# tesis_page1_supply.net
KiCad netlist of a schematic drawn in Altium Designer
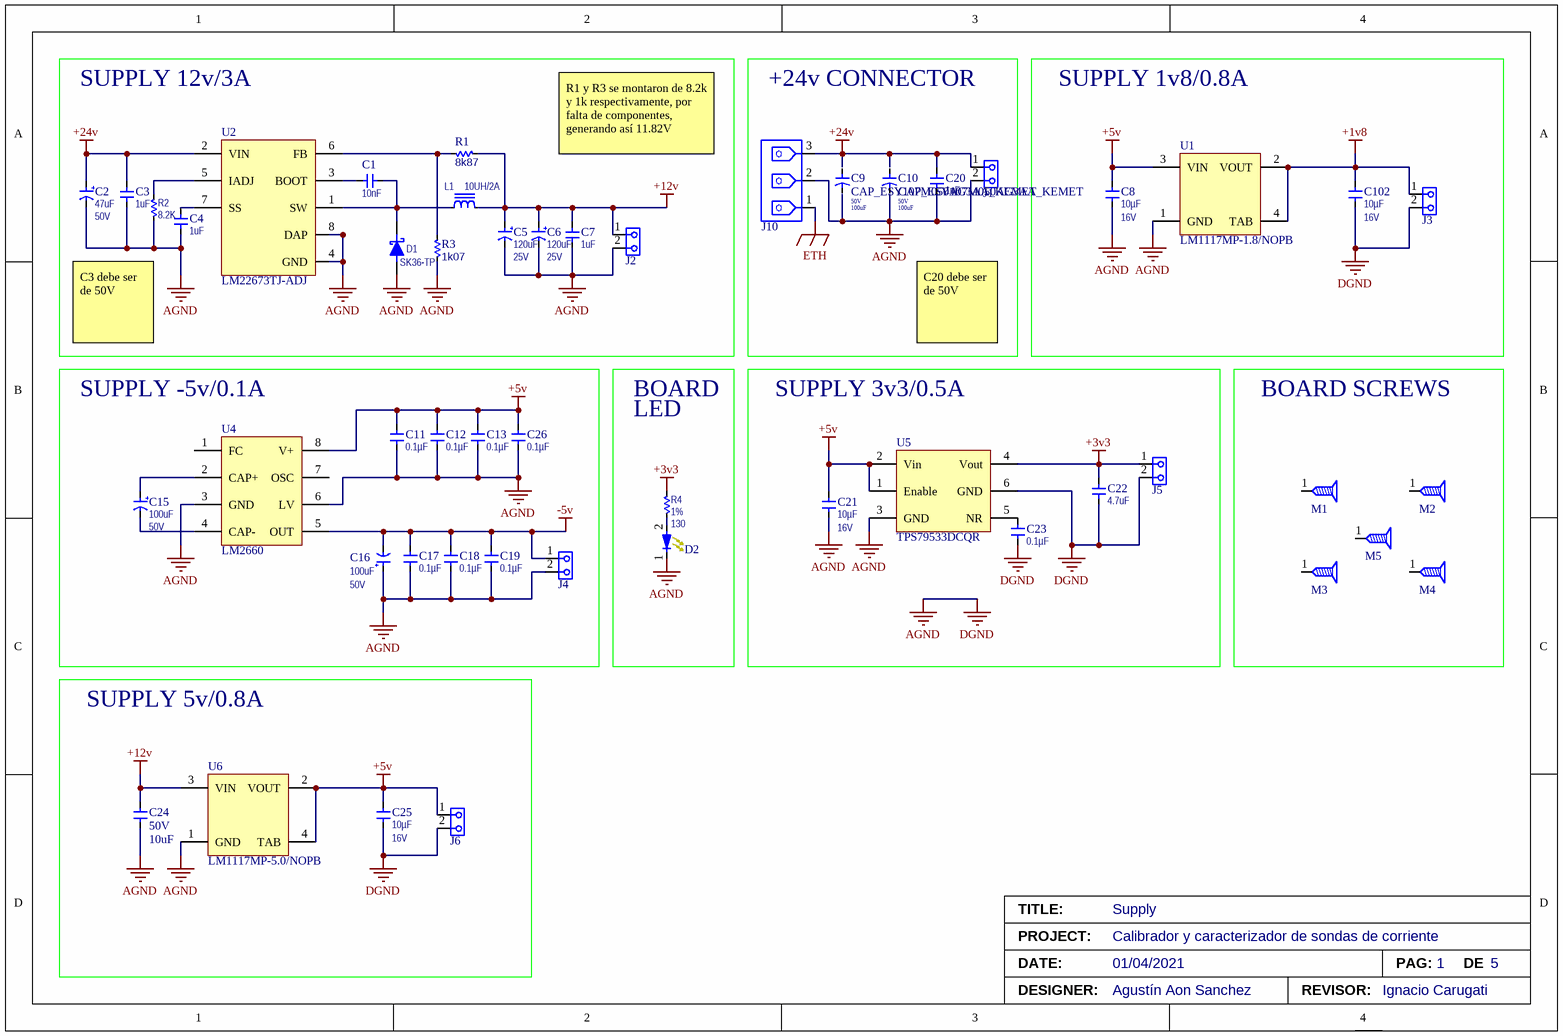
[diagram p0: tesis_page1_supply.SchDoc]

(export (version "E")
  (design (tool "Eeschema 10.0.6"))
  (components
    (comp (ref "C1")
      (value "10nF")
      (footprint "CAPC3216X135N_B")
      (fields
        (field (name "MANUFACTURER") "TDK")
        (field (name "TOLERANCE") "10%")
        (field (name "DIGIKEY PART NUMBER") "445-2291-1-ND")
      )
      (libsource (lib "pqm_v2_lib_cap") (part "CAP_C3216X7R2J103K115AA_TDK"))
    )
    (comp (ref "C2")
      (value "47uF")
      (footprint "CAPAE630770X770N")
      (description "47µF 50V Aluminum Capacitors Radial, Can - SMD 2000 Hrs @ 85°C")
      (fields
        (field (name "MANUFACTURER") "Panasonic")
        (field (name "TOLERANCE") "20%")
        (field (name "VOLTAGE RATING") "50V")
      )
      (libsource (lib "pqm_v2_lib_cap") (part "CAP_EEE-1HA470XP_PANASONIC"))
    )
    (comp (ref "C3")
      (value "1uF")
      (footprint "CAPC3216X135N_B")
      (fields
        (field (name "MANUFACTURER") "TDK")
        (field (name "TOLERANCE") "20%")
        (field (name "DIGIKEY PART NUMBER") "445-4024-1-ND")
      )
      (libsource (lib "pqm_v2_lib_cap") (part "CAP_C3216X7R1E105M085AA_TDK"))
    )
    (comp (ref "C4")
      (value "1uF")
      (footprint "CAPC3216X135N_B")
      (fields
        (field (name "MANUFACTURER") "TDK")
        (field (name "TOLERANCE") "20%")
        (field (name "DIGIKEY PART NUMBER") "445-4024-1-ND")
      )
      (libsource (lib "pqm_v2_lib_cap") (part "CAP_C3216X7R1E105M085AA_TDK"))
    )
    (comp (ref "C5")
      (value "120uF")
      (footprint "CAPPRD250W50D630H1250")
      (description "CAP ALUM 120UF 20% 25V RADIAL")
      (fields
        (field (name "DIGIKEY PART NUMBER") "565-1791-ND")
        (field (name "TOLERANCE") "20%")
        (field (name "VOLTAGE RATING") "25V")
      )
      (libsource (lib "pqm_v2_lib_cap") (part "CAP_ELXY250ELL121MF15D_UC"))
    )
    (comp (ref "C6")
      (value "120uF")
      (footprint "CAPPRD250W50D630H1250")
      (description "CAP ALUM 120UF 20% 25V RADIAL")
      (fields
        (field (name "DIGIKEY PART NUMBER") "565-1791-ND")
        (field (name "TOLERANCE") "20%")
        (field (name "VOLTAGE RATING") "25V")
      )
      (libsource (lib "pqm_v2_lib_cap") (part "CAP_ELXY250ELL121MF15D_UC"))
    )
    (comp (ref "C7")
      (value "1uF")
      (footprint "CAPC3216X135N_B")
      (fields
        (field (name "MANUFACTURER") "TDK")
        (field (name "TOLERANCE") "20%")
        (field (name "DIGIKEY PART NUMBER") "445-4024-1-ND")
      )
      (libsource (lib "pqm_v2_lib_cap") (part "CAP_C3216X7R1E105M085AA_TDK"))
    )
    (comp (ref "C8")
      (value "10µF")
      (footprint "CAPC2013X110N")
      (description "CAP CER 10UF 16V X5R 0805")
      (fields
        (field (name "MANUFACTURER") "Samsung")
        (field (name "TOLERANCE") "10%")
        (field (name "VOLTAGE RATING") "16V")
      )
      (libsource (lib "lib_ic_CAP") (part "CAP_CL21A106KOCL3RC"))
    )
    (comp (ref "C9")
      (value "CAP_ESY107M050AG3AA_KEMET")
      (footprint "cap elec 8x11.5")
      (fields
        (field (name "TOLERANCE") "20%")
        (field (name "VOLTAGE") "50V")
        (field (name "CAPACITANCE") "100uF")
      )
      (libsource (lib "Cap") (part "CAP_ESY107M050AG3AA_KEMET"))
    )
    (comp (ref "C10")
      (value "CAP_ESY107M050AG3AA_KEMET")
      (footprint "cap elec 8x11.5")
      (fields
        (field (name "TOLERANCE") "20%")
        (field (name "VOLTAGE") "50V")
        (field (name "CAPACITANCE") "100uF")
      )
      (libsource (lib "Cap") (part "CAP_ESY107M050AG3AA_KEMET"))
    )
    (comp (ref "C11")
      (value "0.1µF")
      (footprint "CAPC2013X110N")
      (description "CAP CER 0.1UF 25V 10% X7R 0805")
      (fields (field (name "MANUFACTURER") "Yageo") (field (name "DIGIKEY PART NUMBER") "311-1141-1-ND"))
      (libsource (lib "lib_ic_CAP") (part "CAP_CC0805KRX7R8BB104_YAGEO"))
    )
    (comp (ref "C12")
      (value "0.1µF")
      (footprint "CAPC2013X110N")
      (description "CAP CER 0.1UF 25V 10% X7R 0805")
      (fields (field (name "MANUFACTURER") "Yageo") (field (name "DIGIKEY PART NUMBER") "311-1141-1-ND"))
      (libsource (lib "lib_ic_CAP") (part "CAP_CC0805KRX7R8BB104_YAGEO"))
    )
    (comp (ref "C13")
      (value "0.1µF")
      (footprint "CAPC2013X110N")
      (description "CAP CER 0.1UF 25V 10% X7R 0805")
      (fields (field (name "MANUFACTURER") "Yageo") (field (name "DIGIKEY PART NUMBER") "311-1141-1-ND"))
      (libsource (lib "lib_ic_CAP") (part "CAP_CC0805KRX7R8BB104_YAGEO"))
    )
    (comp (ref "C15")
      (value "100uF")
      (footprint "CAPPRD350W60D800H1200")
      (description "CAP ALUM 100UF 20% 50V RADIAL")
      (fields
        (field (name "DIGIKEY PART NUMBER") "399-6119-ND")
        (field (name "TOLERANCE") "20%")
        (field (name "VOLTAGE RATING") "50V")
      )
      (libsource (lib "lib_ic_CAP") (part "CAP_   ESY107M050AG3AA_KEMET"))
    )
    (comp (ref "C16")
      (value "100uF")
      (footprint "CAPPRD350W60D800H1200")
      (description "CAP ALUM 100UF 20% 50V RADIAL")
      (fields
        (field (name "DIGIKEY PART NUMBER") "399-6119-ND")
        (field (name "TOLERANCE") "20%")
        (field (name "VOLTAGE RATING") "50V")
      )
      (libsource (lib "lib_ic_CAP") (part "CAP_   ESY107M050AG3AA_KEMET"))
    )
    (comp (ref "C17")
      (value "0.1µF")
      (footprint "CAPC2013X110N")
      (description "CAP CER 0.1UF 25V 10% X7R 0805")
      (fields (field (name "MANUFACTURER") "Yageo") (field (name "DIGIKEY PART NUMBER") "311-1141-1-ND"))
      (libsource (lib "lib_ic_CAP") (part "CAP_CC0805KRX7R8BB104_YAGEO"))
    )
    (comp (ref "C18")
      (value "0.1µF")
      (footprint "CAPC2013X110N")
      (description "CAP CER 0.1UF 25V 10% X7R 0805")
      (fields (field (name "MANUFACTURER") "Yageo") (field (name "DIGIKEY PART NUMBER") "311-1141-1-ND"))
      (libsource (lib "lib_ic_CAP") (part "CAP_CC0805KRX7R8BB104_YAGEO"))
    )
    (comp (ref "C19")
      (value "0.1µF")
      (footprint "CAPC2013X110N")
      (description "CAP CER 0.1UF 25V 10% X7R 0805")
      (fields (field (name "MANUFACTURER") "Yageo") (field (name "DIGIKEY PART NUMBER") "311-1141-1-ND"))
      (libsource (lib "lib_ic_CAP") (part "CAP_CC0805KRX7R8BB104_YAGEO"))
    )
    (comp (ref "C20")
      (value "1uF")
      (footprint "CAPC3216X135N_B")
      (fields
        (field (name "MANUFACTURER") "TDK")
        (field (name "TOLERANCE") "20%")
        (field (name "DIGIKEY PART NUMBER") "445-4024-1-ND")
      )
      (libsource (lib "lib_ic_CAP") (part "CAP_C3216X7R1E105M085AA_TDK"))
    )
    (comp (ref "C21")
      (value "10µF")
      (footprint "CAPC2013X110N")
      (description "CAP CER 10UF 16V X5R 0805")
      (fields
        (field (name "MANUFACTURER") "Samsung")
        (field (name "TOLERANCE") "10%")
        (field (name "VOLTAGE RATING") "16V")
      )
      (libsource (lib "lib_ic_CAP") (part "CAP_CL21A106KOCL3RC"))
    )
    (comp (ref "C22")
      (value "4.7uF")
      (footprint "CAPC2013X110N")
      (description "CAP CER 4.7UF 25V X5R 0805")
      (fields (field (name "MANUFACTURER") "YAGEO") (field (name "TOLERANCE") "10%"))
      (libsource (lib "lib_ic_CAP") (part "CAP_CC0805KKX5R8BB475_YAGEO_1"))
    )
    (comp (ref "C23")
      (value "0.1µF")
      (footprint "CAPC2013X110N")
      (description "CAP CER 0.1UF 25V 10% X7R 0805")
      (fields (field (name "MANUFACTURER") "Yageo") (field (name "DIGIKEY PART NUMBER") "311-1141-1-ND"))
      (libsource (lib "lib_ic_CAP") (part "CAP_CC0805KRX7R8BB104_YAGEO"))
    )
    (comp (ref "C24")
      (value "10uF")
      (footprint "CAPC3216X135N_B")
      (description "Cap Ceramic 10uF 50V X5R 20% Pad SMD 1206 85C Automotive T/R")
      (fields
        (field (name "MANUFACTURER") "Murata")
        (field (name "TOLERANCE") "20%")
        (field (name "VOLTAGE RATING") "50V")
      )
      (libsource (lib "lib_ic_CAP") (part "CAP_GRT31CR61H106ME01L"))
    )
    (comp (ref "C25")
      (value "10µF")
      (footprint "CAPC2013X110N")
      (description "CAP CER 10UF 16V X5R 0805")
      (fields
        (field (name "MANUFACTURER") "Samsung")
        (field (name "TOLERANCE") "10%")
        (field (name "VOLTAGE RATING") "16V")
      )
      (libsource (lib "lib_ic_CAP") (part "CAP_CL21A106KOCL3RC"))
    )
    (comp (ref "C26")
      (value "0.1µF")
      (footprint "CAPC2013X110N")
      (description "CAP CER 0.1UF 25V 10% X7R 0805")
      (fields (field (name "MANUFACTURER") "Yageo") (field (name "DIGIKEY PART NUMBER") "311-1141-1-ND"))
      (libsource (lib "lib_ic_CAP") (part "CAP_CC0805KRX7R8BB104_YAGEO"))
    )
    (comp (ref "C102")
      (value "10µF")
      (footprint "CAPC2013X110N")
      (description "CAP CER 10UF 16V X5R 0805")
      (fields
        (field (name "MANUFACTURER") "Samsung")
        (field (name "TOLERANCE") "10%")
        (field (name "VOLTAGE RATING") "16V")
      )
      (libsource (lib "lib_ic_CAP") (part "CAP_CL21A106KOCL3RC"))
    )
    (comp (ref "D1")
      (value "SK36-TP")
      (footprint "DIOM7959X262N")
      (description "DIODE SCHOTTKY 60V 3A SMC")
      (fields
        (field (name "MANUFACTURER") "Micro Commercial Co")
        (field (name "DIGIKEY PART NUMBER") "SK36-TPMSCT-ND")
      )
      (libsource (lib "lib_ic_DIO") (part "DIO_SK36_MICROCOM"))
    )
    (comp (ref "D2")
      (value "DIO_150080YS75000_WURTH")
      (footprint "DIO0805")
      (description "LED YELLOW CLEAR 0805 SMD")
      (fields
        (field (name "MANUFACTURER") "Wurth Electronics Inc.")
        (field (name "MANUFACTURER PART NUMBER") "150080YS75000")
      )
      (libsource (lib "lib_ic_DIO") (part "DIO_150080YS75000_WURTH"))
    )
    (comp (ref "J1")
      (value "CON_Header_1x2")
      (footprint "RAD2")
      (libsource (lib "lib_ic_CON") (part "CON_Header_1x2"))
    )
    (comp (ref "J2")
      (value "CON_Header_1x2")
      (footprint "RAD2")
      (libsource (lib "lib_ic_CON") (part "CON_Header_1x2"))
    )
    (comp (ref "J3")
      (value "CON_Header_1x2")
      (footprint "RAD2")
      (libsource (lib "lib_ic_CON") (part "CON_Header_1x2"))
    )
    (comp (ref "J4")
      (value "CON_Header_1x2")
      (footprint "RAD2")
      (libsource (lib "lib_ic_CON") (part "CON_Header_1x2"))
    )
    (comp (ref "J5")
      (value "CON_Header_1x2")
      (footprint "RAD2")
      (libsource (lib "lib_ic_CON") (part "CON_Header_1x2"))
    )
    (comp (ref "J6")
      (value "CON_Header_1x2")
      (footprint "RAD2")
      (libsource (lib "lib_ic_CON") (part "CON_Header_1x2"))
    )
    (comp (ref "J10")
      (value "CON_691137710003")
      (footprint "CON_691137710003")
      (description "TERM BLK 3POS SIDE ENTRY 5MM PCB")
      (fields
        (field (name "MANUFACTURER") "Wurth Electronics")
        (field (name "MANUFACTURER PART NUMBER") "691137710003")
      )
      (libsource (lib "lib_ic_CON") (part "CON_691137710003"))
    )
    (comp (ref "L1")
      (value "10UH/2A")
      (footprint "MAG_INDUCTOR2A")
      (description "FIXED IND 10UH 2A 65 MOHM SMD")
      (fields
        (field (name "MANUFACTURER") "Bourns Inc")
        (field (name "DIGIKEY PART NUMBER") "SRR1005-100MCT-ND")
      )
      (libsource (lib "pqm_v2_lib_mag") (part "MAG_SRR1005-100M_BOURNS"))
    )
    (comp (ref "M1")
      (value "MSC_SCREW")
      (footprint "MH320")
      (description "SCREW")
      (libsource (lib "lib_ic_MSC") (part "MSC_SCREW"))
    )
    (comp (ref "M2")
      (value "MSC_SCREW")
      (footprint "MH320")
      (description "SCREW")
      (libsource (lib "lib_ic_MSC") (part "MSC_SCREW"))
    )
    (comp (ref "M3")
      (value "MSC_SCREW")
      (footprint "MH320")
      (description "SCREW")
      (libsource (lib "lib_ic_MSC") (part "MSC_SCREW"))
    )
    (comp (ref "M4")
      (value "MSC_SCREW")
      (footprint "MH320")
      (description "SCREW")
      (libsource (lib "lib_ic_MSC") (part "MSC_SCREW"))
    )
    (comp (ref "M5")
      (value "MSC_SCREW")
      (footprint "MH320")
      (description "SCREW")
      (libsource (lib "lib_ic_MSC") (part "MSC_SCREW"))
    )
    (comp (ref "R1")
      (value "8k87")
      (footprint "RESC2013X065BN")
      (description "Res Thick Film 0805 8.87K Ohm 1% 0.125W(1/8W) ±100ppm/C Epoxy Pad SMD T/R")
      (fields
        (field (name "MANUFACTURER") "Yageo")
        (field (name "MANUFACTURER PART NUMBER") "RC0805FR-078K87L")
      )
      (libsource (lib "lib_ic_RES") (part "RES_RC0805FR-078K87L"))
    )
    (comp (ref "R2")
      (value "8.2K")
      (footprint "RESC3216N")
      (description "RES SMD 8.2K OHM 5% 1/4W 1206")
      (fields (field (name "TOLERANCE") "5%") (field (name "MANUFACTURER") "Panasonic"))
      (libsource (lib "pqm_v2_lib_res") (part "RES_ERJ-8GEYJ822V_Panasonic"))
    )
    (comp (ref "R3")
      (value "1k07")
      (footprint "RESC2013X065BN")
      (description "Res Thick Film 0805 1.07K Ohm 1% 1/8W 100ppm/C Molded SMD Paper T/R")
      (fields
        (field (name "MANUFACTURER") "Yageo")
        (field (name "MANUFACTURER PART NUMBER") "RC0805FR-071K07L")
      )
      (libsource (lib "lib_ic_RES") (part "RES_RC0805FR-071K07L"))
    )
    (comp (ref "R4")
      (value "130")
      (footprint "RESC2013X065BN")
      (description "RES SMD 130 OHM 1% 1/8W 0805")
      (fields
        (field (name "MANUFACTURER") "Yageo")
        (field (name "DIGIKEY PART NUMBER") "311-130CRCT-ND")
        (field (name "TOLERANCE") "1%")
      )
      (libsource (lib "lib_ic_RES") (part "RES_RC0805FR-07130RL_YAGEO"))
    )
    (comp (ref "U1")
      (value "LM1117MP-1.8/NOPB")
      (footprint "SOT223-3L")
      (description "IC REG LDO 1.8V .8A SOT-223-4")
      (fields (field (name "MANUFACTURER") "TI National Semiconductor"))
      (libsource (lib "lib_ic_IC") (part "IC_LM1117MP-1.8/NOPB"))
    )
    (comp (ref "U2")
      (value "LM22673TJ-ADJ")
      (footprint "TJ7A_N")
      (fields
        (field (name "DIGIKEY PART NUMBER") "LM22673TJ-ADJ/NOPBCT-ND")
        (field (name "MANUFACTURER PART NUMBER") "LM22673TJ-ADJ/NOPB")
        (field (name "MOUSER PART NUMBER") "926-LM22673TJADJNOPB")
      )
      (libsource (lib "lib_ic_IC") (part "IC_LM22673TJ-ADJ"))
    )
    (comp (ref "U4")
      (value "LM2660")
      (footprint "SOIC127P600-8BN")
      (description "IC REG SWTCHD CAP INV 0.1A 8SOIC")
      (fields
        (field (name "DIGIKEY PART NUMBER") "LM2660MX/NOPBCT-ND")
        (field (name "MANUFACTURER PART NUMBER") "LM2660MX/NOPB")
      )
      (libsource (lib "lib_ic_IC") (part "IC_LM2660MX/NOPB_1"))
    )
    (comp (ref "U5")
      (value "TPS79533DCQR")
      (footprint "SOT223-6L")
      (description "IC REG LIN 3.3V 500MA SOT223-6")
      (fields
        (field (name "DIGIKEY PART NUMBER") "296-13810-1-ND")
        (field (name "MANUFACTURER PART NUMBER") "595-TPS79533DCQR")
      )
      (libsource (lib "lib_ic_IC") (part "IC_TPS79533DCQR_TI"))
    )
    (comp (ref "U6")
      (value "LM1117MP-5.0/NOPB")
      (footprint "SOT223-3L")
      (description "IC REG LDO 5V .8A SOT-223-4")
      (fields (field (name "MANUFACTURER") "TI National Semiconductor"))
      (libsource (lib "lib_ic_IC") (part "IC_LM1117MP-5.0/NOPB"))
    )
  )
  (nets
    (net (code "1") (name "+1v8") (class "Default")
      (node (ref "C102") (pin "1") (pinfunction "T1_1") (pintype "passive"))
      (node (ref "J3") (pin "1") (pinfunction "1_1") (pintype "passive"))
      (node (ref "U1") (pin "2") (pinfunction "VOUT_2") (pintype "passive"))
      (node (ref "U1") (pin "4") (pinfunction "TAB_4") (pintype "passive"))
    )
    (net (code "2") (name "+3v3") (class "Default")
      (node (ref "C22") (pin "1") (pinfunction "T1_1") (pintype "passive"))
      (node (ref "J5") (pin "1") (pinfunction "1_1") (pintype "passive"))
      (node (ref "R4") (pin "2") (pinfunction "T2_2") (pintype "passive"))
      (node (ref "U5") (pin "4") (pinfunction "Vout_4") (pintype "passive"))
    )
    (net (code "3") (name "+5v") (class "Default")
      (node (ref "C11") (pin "1") (pinfunction "T1_1") (pintype "passive"))
      (node (ref "C12") (pin "1") (pinfunction "T1_1") (pintype "passive"))
      (node (ref "C13") (pin "1") (pinfunction "T1_1") (pintype "passive"))
      (node (ref "C21") (pin "1") (pinfunction "T1_1") (pintype "passive"))
      (node (ref "C25") (pin "1") (pinfunction "T1_1") (pintype "passive"))
      (node (ref "C26") (pin "1") (pinfunction "T1_1") (pintype "passive"))
      (node (ref "C8") (pin "1") (pinfunction "T1_1") (pintype "passive"))
      (node (ref "J6") (pin "1") (pinfunction "1_1") (pintype "passive"))
      (node (ref "U1") (pin "3") (pinfunction "VIN_3") (pintype "passive"))
      (node (ref "U4") (pin "8") (pinfunction "V+_8") (pintype "passive"))
      (node (ref "U5") (pin "1") (pinfunction "Enable_1") (pintype "passive"))
      (node (ref "U5") (pin "2") (pinfunction "Vin_2") (pintype "passive"))
      (node (ref "U6") (pin "2") (pinfunction "VOUT_2") (pintype "passive"))
      (node (ref "U6") (pin "4") (pinfunction "TAB_4") (pintype "passive"))
    )
    (net (code "4") (name "+12v") (class "Default")
      (node (ref "C24") (pin "1") (pinfunction "T1_1") (pintype "passive"))
      (node (ref "C5") (pin "1") (pinfunction "1_1") (pintype "passive"))
      (node (ref "C6") (pin "1") (pinfunction "1_1") (pintype "passive"))
      (node (ref "C7") (pin "1") (pinfunction "T1_1") (pintype "passive"))
      (node (ref "J2") (pin "1") (pinfunction "1_1") (pintype "passive"))
      (node (ref "L1") (pin "2") (pinfunction "2_2") (pintype "passive"))
      (node (ref "R1") (pin "1") (pinfunction "T1_1") (pintype "passive"))
      (node (ref "U6") (pin "3") (pinfunction "VIN_3") (pintype "passive"))
    )
    (net (code "5") (name "+24v") (class "Default")
      (node (ref "C2") (pin "1") (pinfunction "1_1") (pintype "passive"))
      (node (ref "C20") (pin "1") (pinfunction "T1_1") (pintype "passive"))
      (node (ref "C3") (pin "1") (pinfunction "T1_1") (pintype "passive"))
      (node (ref "J1") (pin "1") (pinfunction "1_1") (pintype "passive"))
      (node (ref "J10") (pin "3") (pinfunction "3_3") (pintype "passive"))
      (node (ref "U2") (pin "2") (pinfunction "VIN_2") (pintype "power_in"))
    )
    (net (code "6") (name "-5v") (class "Default")
      (node (ref "C16") (pin "2") (pinfunction "2_2") (pintype "passive"))
      (node (ref "C17") (pin "1") (pinfunction "T1_1") (pintype "passive"))
      (node (ref "C18") (pin "1") (pinfunction "T1_1") (pintype "passive"))
      (node (ref "C19") (pin "1") (pinfunction "T1_1") (pintype "passive"))
      (node (ref "J4") (pin "1") (pinfunction "1_1") (pintype "passive"))
      (node (ref "U4") (pin "5") (pinfunction "OUT_5") (pintype "passive"))
    )
    (net (code "7") (name "AGND") (class "Default")
      (node (ref "C102") (pin "2") (pinfunction "T2_2") (pintype "passive"))
      (node (ref "C11") (pin "2") (pinfunction "T2_2") (pintype "passive"))
      (node (ref "C12") (pin "2") (pinfunction "T2_2") (pintype "passive"))
      (node (ref "C13") (pin "2") (pinfunction "T2_2") (pintype "passive"))
      (node (ref "C16") (pin "1") (pinfunction "1_1") (pintype "passive"))
      (node (ref "C17") (pin "2") (pinfunction "T2_2") (pintype "passive"))
      (node (ref "C18") (pin "2") (pinfunction "T2_2") (pintype "passive"))
      (node (ref "C19") (pin "2") (pinfunction "T2_2") (pintype "passive"))
      (node (ref "C2") (pin "2") (pinfunction "2_2") (pintype "passive"))
      (node (ref "C20") (pin "2") (pinfunction "T2_2") (pintype "passive"))
      (node (ref "C21") (pin "2") (pinfunction "T2_2") (pintype "passive"))
      (node (ref "C22") (pin "2") (pinfunction "T2_2") (pintype "passive"))
      (node (ref "C23") (pin "2") (pinfunction "T2_2") (pintype "passive"))
      (node (ref "C24") (pin "2") (pinfunction "T2_2") (pintype "passive"))
      (node (ref "C25") (pin "2") (pinfunction "T2_2") (pintype "passive"))
      (node (ref "C26") (pin "2") (pinfunction "T2_2") (pintype "passive"))
      (node (ref "C3") (pin "2") (pinfunction "T2_2") (pintype "passive"))
      (node (ref "C4") (pin "2") (pinfunction "T2_2") (pintype "passive"))
      (node (ref "C5") (pin "2") (pinfunction "2_2") (pintype "passive"))
      (node (ref "C6") (pin "2") (pinfunction "2_2") (pintype "passive"))
      (node (ref "C7") (pin "2") (pinfunction "T2_2") (pintype "passive"))
      (node (ref "C8") (pin "2") (pinfunction "T2_2") (pintype "passive"))
      (node (ref "D1") (pin "2") (pinfunction "A_2") (pintype "passive"))
      (node (ref "D2") (pin "1") (pinfunction "Cathode_1") (pintype "passive"))
      (node (ref "J1") (pin "2") (pinfunction "2_2") (pintype "passive"))
      (node (ref "J10") (pin "2") (pinfunction "2_2") (pintype "passive"))
      (node (ref "J2") (pin "2") (pinfunction "2_2") (pintype "passive"))
      (node (ref "J3") (pin "2") (pinfunction "2_2") (pintype "passive"))
      (node (ref "J4") (pin "2") (pinfunction "2_2") (pintype "passive"))
      (node (ref "J5") (pin "2") (pinfunction "2_2") (pintype "passive"))
      (node (ref "J6") (pin "2") (pinfunction "2_2") (pintype "passive"))
      (node (ref "R2") (pin "1") (pinfunction "T1_1") (pintype "passive"))
      (node (ref "R3") (pin "1") (pinfunction "T1_1") (pintype "passive"))
      (node (ref "U1") (pin "1") (pinfunction "GND_1") (pintype "passive"))
      (node (ref "U2") (pin "4") (pinfunction "GND_4") (pintype "power_in"))
      (node (ref "U2") (pin "8") (pinfunction "DAP_8") (pintype "power_in"))
      (node (ref "U4") (pin "3") (pinfunction "GND_3") (pintype "passive"))
      (node (ref "U4") (pin "6") (pinfunction "LV_6") (pintype "passive"))
      (node (ref "U5") (pin "3") (pinfunction "GND_3") (pintype "passive"))
      (node (ref "U5") (pin "6") (pinfunction "GND_6") (pintype "passive"))
      (node (ref "U6") (pin "1") (pinfunction "GND_1") (pintype "passive"))
    )
    (net (code "8") (name "ETH") (class "Default")
      (node (ref "J10") (pin "1") (pinfunction "1_1") (pintype "passive"))
    )
    (net (code "9") (name "Net-(C1-T1)") (class "Default")
      (node (ref "C1") (pin "1") (pinfunction "T1_1") (pintype "passive"))
      (node (ref "U2") (pin "3") (pinfunction "BOOT_3") (pintype "passive"))
    )
    (net (code "10") (name "Net-(C1-T2)") (class "Default")
      (node (ref "C1") (pin "2") (pinfunction "T2_2") (pintype "passive"))
      (node (ref "D1") (pin "1") (pinfunction "K_1") (pintype "passive"))
      (node (ref "L1") (pin "1") (pinfunction "1_1") (pintype "passive"))
      (node (ref "U2") (pin "1") (pinfunction "SW_1") (pintype "power_in"))
    )
    (net (code "11") (name "Net-(C4-T1)") (class "Default")
      (node (ref "C4") (pin "1") (pinfunction "T1_1") (pintype "passive"))
      (node (ref "U2") (pin "7") (pinfunction "SS_7") (pintype "power_in"))
    )
    (net (code "12") (name "Net-(C23-T1)") (class "Default")
      (node (ref "C23") (pin "1") (pinfunction "T1_1") (pintype "passive"))
      (node (ref "U5") (pin "5") (pinfunction "NR_5") (pintype "passive"))
    )
    (net (code "13") (name "Net-(D2-Anode)") (class "Default")
      (node (ref "D2") (pin "2") (pinfunction "Anode_2") (pintype "passive"))
      (node (ref "R4") (pin "1") (pinfunction "T1_1") (pintype "passive"))
    )
    (net (code "14") (name "Net-(R1-T2)") (class "Default")
      (node (ref "R1") (pin "2") (pinfunction "T2_2") (pintype "passive"))
      (node (ref "R3") (pin "2") (pinfunction "T2_2") (pintype "passive"))
      (node (ref "U2") (pin "6") (pinfunction "FB_6") (pintype "power_in"))
    )
    (net (code "15") (name "Net-(R2-T2)") (class "Default")
      (node (ref "R2") (pin "2") (pinfunction "T2_2") (pintype "passive"))
      (node (ref "U2") (pin "5") (pinfunction "IADJ_5") (pintype "power_in"))
    )
    (net (code "16") (name "Net-(U4-CAP+)") (class "Default")
      (node (ref "C15") (pin "1") (pinfunction "1_1") (pintype "passive"))
      (node (ref "U4") (pin "2") (pinfunction "CAP+_2") (pintype "passive"))
    )
    (net (code "17") (name "Net-(U4-CAP-)") (class "Default")
      (node (ref "C15") (pin "2") (pinfunction "2_2") (pintype "passive"))
      (node (ref "U4") (pin "4") (pinfunction "CAP-_4") (pintype "power_in"))
    )
    (net (code "18") (name "unconnected-(C9-Pad24)") (class "Default")
      (node (ref "C9") (pin "24") (pinfunction "24_24") (pintype "passive"))
    )
    (net (code "19") (name "unconnected-(C9-Pad25)") (class "Default")
      (node (ref "C9") (pin "25") (pinfunction "25_25") (pintype "passive"))
    )
    (net (code "20") (name "unconnected-(C10-Pad24)") (class "Default")
      (node (ref "C10") (pin "24") (pinfunction "24_24") (pintype "passive"))
    )
    (net (code "21") (name "unconnected-(C10-Pad25)") (class "Default")
      (node (ref "C10") (pin "25") (pinfunction "25_25") (pintype "passive"))
    )
    (net (code "22") (name "unconnected-(M1-Pad1)") (class "Default")
      (node (ref "M1") (pin "1") (pinfunction "1_1") (pintype "power_in"))
    )
    (net (code "23") (name "unconnected-(M2-Pad1)") (class "Default")
      (node (ref "M2") (pin "1") (pinfunction "1_1") (pintype "power_in"))
    )
    (net (code "24") (name "unconnected-(M3-Pad1)") (class "Default")
      (node (ref "M3") (pin "1") (pinfunction "1_1") (pintype "power_in"))
    )
    (net (code "25") (name "unconnected-(M4-Pad1)") (class "Default")
      (node (ref "M4") (pin "1") (pinfunction "1_1") (pintype "power_in"))
    )
    (net (code "26") (name "unconnected-(M5-Pad1)") (class "Default")
      (node (ref "M5") (pin "1") (pinfunction "1_1") (pintype "power_in"))
    )
    (net (code "27") (name "unconnected-(U4-FC-Pad1)") (class "Default")
      (node (ref "U4") (pin "1") (pinfunction "FC_1") (pintype "passive"))
    )
    (net (code "28") (name "unconnected-(U4-OSC-Pad7)") (class "Default")
      (node (ref "U4") (pin "7") (pinfunction "OSC_7") (pintype "power_in"))
    )
  )
)
